# 3_-MAIN.net
KiCad netlist of a schematic drawn in Altium Designer
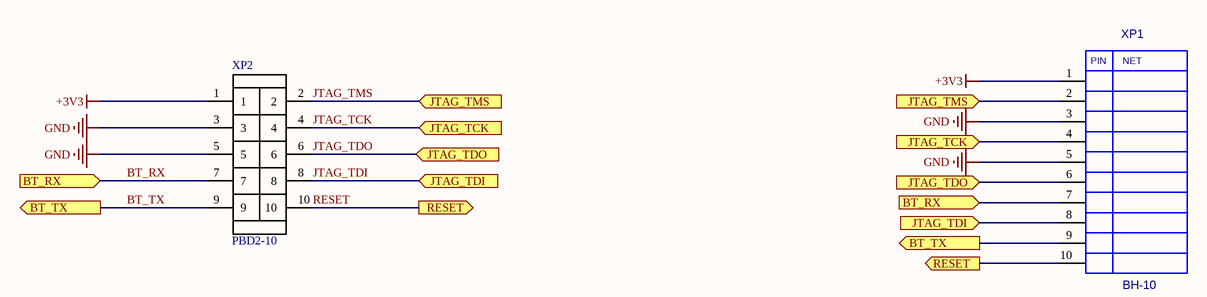
[diagram p0: [3]-MAIN.SchDoc]

(export (version "E")
  (design (tool "Eeschema 10.0.6"))
  (components
    (comp (ref "XP1") (value "BH-10") (footprint "BH-10") (libsource (lib "fizik_lib") (part "BH-10")))
    (comp (ref "XP2")
      (value "PBD2-10")
      (footprint "PLD2-10")
      (libsource (lib "gprs_modem_2") (part "PLD2-10"))
    )
  )
  (nets
    (net (code "1") (name "+3V3") (class "Default")
      (node (ref "XP1") (pin "1") (pinfunction "1_1") (pintype "passive"))
      (node (ref "XP2") (pin "1") (pinfunction "1_1") (pintype "passive"))
    )
    (net (code "2") (name "/BT_RX") (class "Default")
      (node (ref "XP1") (pin "7") (pinfunction "7_7") (pintype "passive"))
      (node (ref "XP2") (pin "7") (pinfunction "7_7") (pintype "passive"))
    )
    (net (code "3") (name "/BT_TX") (class "Default")
      (node (ref "XP1") (pin "9") (pinfunction "9_9") (pintype "passive"))
      (node (ref "XP2") (pin "9") (pinfunction "9_9") (pintype "passive"))
    )
    (net (code "4") (name "/JTAG_TCK") (class "Default")
      (node (ref "XP1") (pin "4") (pinfunction "4_4") (pintype "passive"))
      (node (ref "XP2") (pin "4") (pinfunction "4_4") (pintype "passive"))
    )
    (net (code "5") (name "/JTAG_TDI") (class "Default")
      (node (ref "XP1") (pin "8") (pinfunction "8_8") (pintype "passive"))
      (node (ref "XP2") (pin "8") (pinfunction "8_8") (pintype "passive"))
    )
    (net (code "6") (name "/JTAG_TDO") (class "Default")
      (node (ref "XP1") (pin "6") (pinfunction "6_6") (pintype "passive"))
      (node (ref "XP2") (pin "6") (pinfunction "6_6") (pintype "passive"))
    )
    (net (code "7") (name "/JTAG_TMS") (class "Default")
      (node (ref "XP1") (pin "2") (pinfunction "2_2") (pintype "passive"))
      (node (ref "XP2") (pin "2") (pinfunction "2_2") (pintype "passive"))
    )
    (net (code "8") (name "/RESET") (class "Default")
      (node (ref "XP1") (pin "10") (pinfunction "10_10") (pintype "passive"))
      (node (ref "XP2") (pin "10") (pinfunction "10_10") (pintype "passive"))
    )
    (net (code "9") (name "GND") (class "Default")
      (node (ref "XP1") (pin "3") (pinfunction "3_3") (pintype "passive"))
      (node (ref "XP1") (pin "5") (pinfunction "5_5") (pintype "passive"))
      (node (ref "XP2") (pin "3") (pinfunction "3_3") (pintype "passive"))
      (node (ref "XP2") (pin "5") (pinfunction "5_5") (pintype "passive"))
    )
  )
)
